# MCUs.net
KiCad netlist of a schematic drawn in Altium Designer
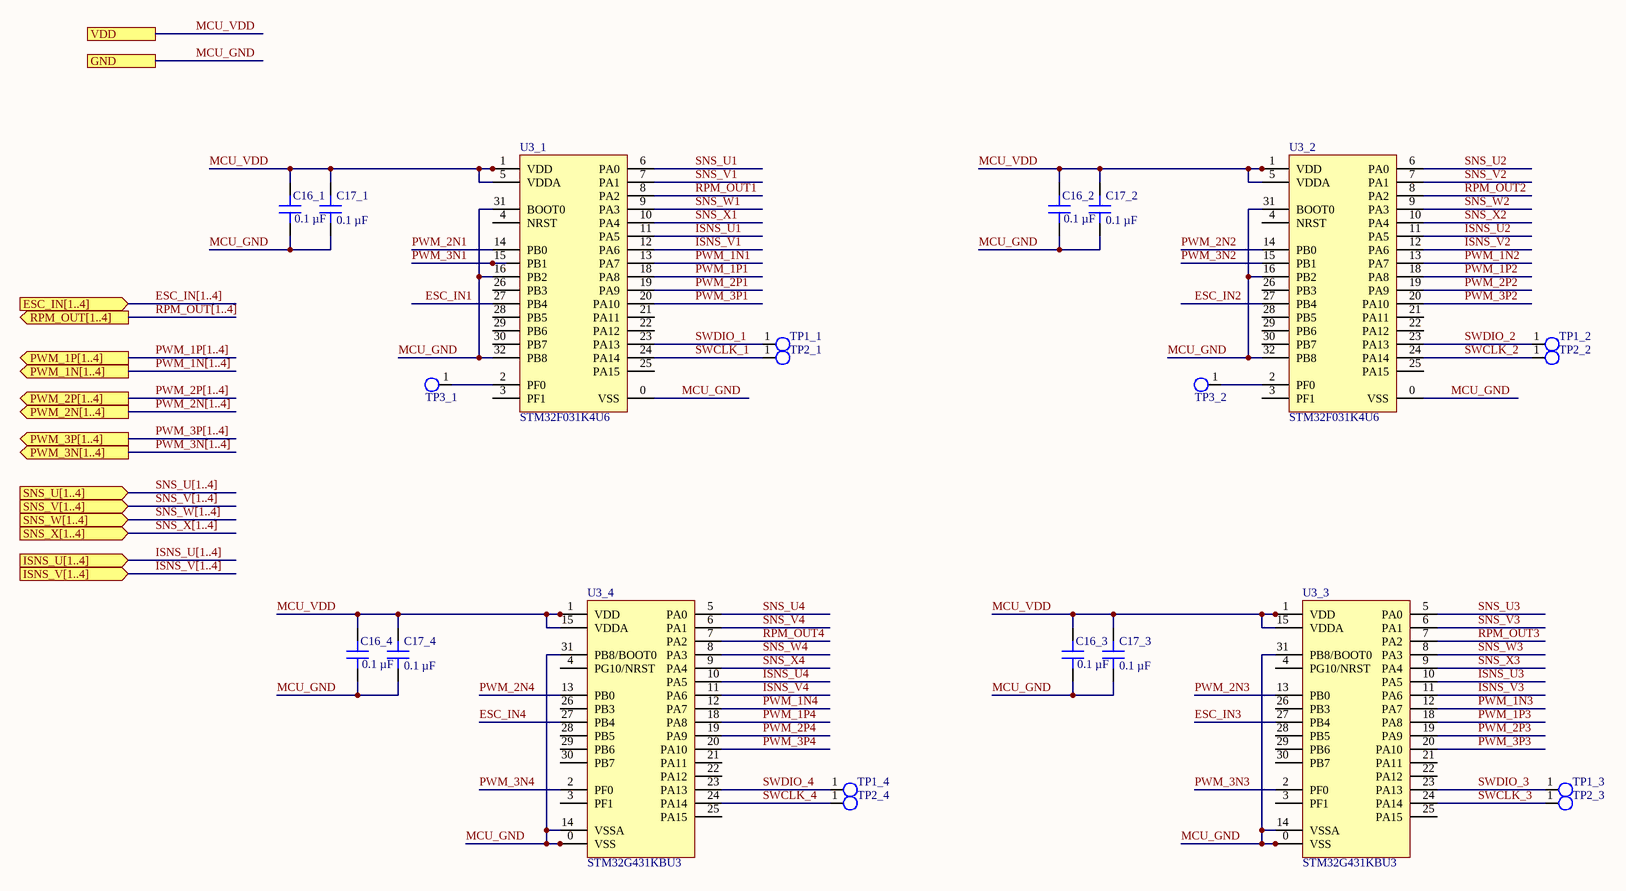
[diagram p0: MCUs.SchDoc]

(export (version "E")
  (design (tool "Eeschema 10.0.6"))
  (components
    (comp (ref "C16_1")
      (value "0.1 µF")
      (footprint "CAP 0402_1005")
      (description "CAP CER 0.1UF 16V X7R 0402")
      (fields (field (name "PART NUMBER") "C0402C104K4RACAUTO") (field (name "MANUFACTURER") "KEMET"))
      (libsource (lib "Celestial Altium Library - altium_library") (part "Capacitor"))
    )
    (comp (ref "C16_2")
      (value "0.1 µF")
      (footprint "CAP 0402_1005")
      (description "CAP CER 0.1UF 16V X7R 0402")
      (fields (field (name "PART NUMBER") "C0402C104K4RACAUTO") (field (name "MANUFACTURER") "KEMET"))
      (libsource (lib "Celestial Altium Library - altium_library") (part "Capacitor"))
    )
    (comp (ref "C16_3")
      (value "0.1 µF")
      (footprint "CAP 0402_1005")
      (description "CAP CER 0.1UF 16V X7R 0402")
      (fields (field (name "PART NUMBER") "C0402C104K4RACAUTO") (field (name "MANUFACTURER") "KEMET"))
      (libsource (lib "Celestial Altium Library - altium_library") (part "Capacitor"))
    )
    (comp (ref "C16_4")
      (value "0.1 µF")
      (footprint "CAP 0402_1005")
      (description "CAP CER 0.1UF 16V X7R 0402")
      (fields (field (name "PART NUMBER") "C0402C104K4RACAUTO") (field (name "MANUFACTURER") "KEMET"))
      (libsource (lib "Celestial Altium Library - altium_library") (part "Capacitor"))
    )
    (comp (ref "C17_1")
      (value "0.1 µF")
      (footprint "CAP 0402_1005")
      (description "CAP CER 0.1UF 16V X7R 0402")
      (fields (field (name "PART NUMBER") "C0402C104K4RACAUTO") (field (name "MANUFACTURER") "KEMET"))
      (libsource (lib "Celestial Altium Library - altium_library") (part "Capacitor"))
    )
    (comp (ref "C17_2")
      (value "0.1 µF")
      (footprint "CAP 0402_1005")
      (description "CAP CER 0.1UF 16V X7R 0402")
      (fields (field (name "PART NUMBER") "C0402C104K4RACAUTO") (field (name "MANUFACTURER") "KEMET"))
      (libsource (lib "Celestial Altium Library - altium_library") (part "Capacitor"))
    )
    (comp (ref "C17_3")
      (value "0.1 µF")
      (footprint "CAP 0402_1005")
      (description "CAP CER 0.1UF 16V X7R 0402")
      (fields (field (name "PART NUMBER") "C0402C104K4RACAUTO") (field (name "MANUFACTURER") "KEMET"))
      (libsource (lib "Celestial Altium Library - altium_library") (part "Capacitor"))
    )
    (comp (ref "C17_4")
      (value "0.1 µF")
      (footprint "CAP 0402_1005")
      (description "CAP CER 0.1UF 16V X7R 0402")
      (fields (field (name "PART NUMBER") "C0402C104K4RACAUTO") (field (name "MANUFACTURER") "KEMET"))
      (libsource (lib "Celestial Altium Library - altium_library") (part "Capacitor"))
    )
    (comp (ref "TP1_1")
      (value "0.635mm")
      (footprint "TP  0.635mm")
      (description "Test point")
      (libsource (lib "IC") (part "TP 0.635mm"))
    )
    (comp (ref "TP1_2")
      (value "0.635mm")
      (footprint "TP  0.635mm")
      (description "Test point")
      (libsource (lib "IC") (part "TP 0.635mm"))
    )
    (comp (ref "TP1_3")
      (value "0.635mm")
      (footprint "TP  0.635mm")
      (description "Test point")
      (libsource (lib "IC") (part "TP 0.635mm"))
    )
    (comp (ref "TP1_4")
      (value "0.635mm")
      (footprint "TP  0.635mm")
      (description "Test point")
      (libsource (lib "IC") (part "TP 0.635mm"))
    )
    (comp (ref "TP2_1")
      (value "0.635mm")
      (footprint "TP  0.635mm")
      (description "Test point")
      (libsource (lib "IC") (part "TP 0.635mm"))
    )
    (comp (ref "TP2_2")
      (value "0.635mm")
      (footprint "TP  0.635mm")
      (description "Test point")
      (libsource (lib "IC") (part "TP 0.635mm"))
    )
    (comp (ref "TP2_3")
      (value "0.635mm")
      (footprint "TP  0.635mm")
      (description "Test point")
      (libsource (lib "IC") (part "TP 0.635mm"))
    )
    (comp (ref "TP2_4")
      (value "0.635mm")
      (footprint "TP  0.635mm")
      (description "Test point")
      (libsource (lib "IC") (part "TP 0.635mm"))
    )
    (comp (ref "TP3_1")
      (value "0.635mm")
      (footprint "TP  0.635mm")
      (description "Test point")
      (libsource (lib "IC") (part "TP 0.635mm"))
    )
    (comp (ref "TP3_2")
      (value "0.635mm")
      (footprint "TP  0.635mm")
      (description "Test point")
      (libsource (lib "IC") (part "TP 0.635mm"))
    )
    (comp (ref "U3_1")
      (value "STM32F031K4U6")
      (footprint "QFN50P400X400X60-32N")
      (description "MCU UFQFPN-32")
      (libsource (lib "IC") (part "STM32F031K4U6"))
    )
    (comp (ref "U3_2")
      (value "STM32F031K4U6")
      (footprint "QFN50P400X400X60-32N")
      (description "MCU UFQFPN-32")
      (libsource (lib "IC") (part "STM32F031K4U6"))
    )
    (comp (ref "U3_3")
      (value "STM32G431KBU3")
      (footprint "QFN50P400X400X60-32N")
      (description "MCU UFQFPN-32")
      (libsource (lib "IC") (part "STM32G431KBU3"))
    )
    (comp (ref "U3_4")
      (value "STM32G431KBU3")
      (footprint "QFN50P400X400X60-32N")
      (description "MCU UFQFPN-32")
      (libsource (lib "IC") (part "STM32G431KBU3"))
    )
  )
  (nets
    (net (code "1") (name "/ESC_IN1") (class "Default")
      (node (ref "U3_1") (pin "27") (pinfunction "PB4_27") (pintype "passive"))
    )
    (net (code "2") (name "/ESC_IN2") (class "Default")
      (node (ref "U3_2") (pin "27") (pinfunction "PB4_27") (pintype "passive"))
    )
    (net (code "3") (name "/ESC_IN3") (class "Default")
      (node (ref "U3_3") (pin "27") (pinfunction "PB4_27") (pintype "passive"))
    )
    (net (code "4") (name "/ESC_IN4") (class "Default")
      (node (ref "U3_4") (pin "27") (pinfunction "PB4_27") (pintype "passive"))
    )
    (net (code "6") (name "/ISNS_U1") (class "Default")
      (node (ref "U3_1") (pin "11") (pinfunction "PA5_11") (pintype "passive"))
    )
    (net (code "7") (name "/ISNS_U2") (class "Default")
      (node (ref "U3_2") (pin "11") (pinfunction "PA5_11") (pintype "passive"))
    )
    (net (code "8") (name "/ISNS_U3") (class "Default")
      (node (ref "U3_3") (pin "10") (pinfunction "PA5_10") (pintype "passive"))
    )
    (net (code "9") (name "/ISNS_U4") (class "Default")
      (node (ref "U3_4") (pin "10") (pinfunction "PA5_10") (pintype "passive"))
    )
    (net (code "11") (name "/ISNS_V1") (class "Default")
      (node (ref "U3_1") (pin "12") (pinfunction "PA6_12") (pintype "passive"))
    )
    (net (code "12") (name "/ISNS_V2") (class "Default")
      (node (ref "U3_2") (pin "12") (pinfunction "PA6_12") (pintype "passive"))
    )
    (net (code "13") (name "/ISNS_V3") (class "Default")
      (node (ref "U3_3") (pin "11") (pinfunction "PA6_11") (pintype "passive"))
    )
    (net (code "14") (name "/ISNS_V4") (class "Default")
      (node (ref "U3_4") (pin "11") (pinfunction "PA6_11") (pintype "passive"))
    )
    (net (code "16") (name "/MCU_GND") (class "Default")
      (node (ref "C16_1") (pin "1") (pinfunction "1_1") (pintype "passive"))
      (node (ref "C16_2") (pin "1") (pinfunction "1_1") (pintype "passive"))
      (node (ref "C16_3") (pin "1") (pinfunction "1_1") (pintype "passive"))
      (node (ref "C16_4") (pin "1") (pinfunction "1_1") (pintype "passive"))
      (node (ref "C17_1") (pin "1") (pinfunction "1_1") (pintype "passive"))
      (node (ref "C17_2") (pin "1") (pinfunction "1_1") (pintype "passive"))
      (node (ref "C17_3") (pin "1") (pinfunction "1_1") (pintype "passive"))
      (node (ref "C17_4") (pin "1") (pinfunction "1_1") (pintype "passive"))
      (node (ref "U3_1") (pin "0") (pinfunction "VSS_0") (pintype "passive"))
      (node (ref "U3_1") (pin "16") (pinfunction "PB2_16") (pintype "passive"))
      (node (ref "U3_1") (pin "31") (pinfunction "BOOT0_31") (pintype "passive"))
      (node (ref "U3_1") (pin "32") (pinfunction "PB8_32") (pintype "passive"))
      (node (ref "U3_2") (pin "0") (pinfunction "VSS_0") (pintype "passive"))
      (node (ref "U3_2") (pin "16") (pinfunction "PB2_16") (pintype "passive"))
      (node (ref "U3_2") (pin "31") (pinfunction "BOOT0_31") (pintype "passive"))
      (node (ref "U3_2") (pin "32") (pinfunction "PB8_32") (pintype "passive"))
      (node (ref "U3_3") (pin "0") (pinfunction "VSS_0") (pintype "passive"))
      (node (ref "U3_3") (pin "14") (pinfunction "VSSA_14") (pintype "passive"))
      (node (ref "U3_3") (pin "16") (pinfunction "VSS_16") (pintype "passive"))
      (node (ref "U3_3") (pin "31") (pinfunction "PB8/BOOT0_31") (pintype "passive"))
      (node (ref "U3_3") (pin "32") (pinfunction "VSS_32") (pintype "passive"))
      (node (ref "U3_4") (pin "0") (pinfunction "VSS_0") (pintype "passive"))
      (node (ref "U3_4") (pin "14") (pinfunction "VSSA_14") (pintype "passive"))
      (node (ref "U3_4") (pin "16") (pinfunction "VSS_16") (pintype "passive"))
      (node (ref "U3_4") (pin "31") (pinfunction "PB8/BOOT0_31") (pintype "passive"))
      (node (ref "U3_4") (pin "32") (pinfunction "VSS_32") (pintype "passive"))
    )
    (net (code "17") (name "/MCU_VDD") (class "Default")
      (node (ref "C16_1") (pin "2") (pinfunction "2_2") (pintype "passive"))
      (node (ref "C16_2") (pin "2") (pinfunction "2_2") (pintype "passive"))
      (node (ref "C16_3") (pin "2") (pinfunction "2_2") (pintype "passive"))
      (node (ref "C16_4") (pin "2") (pinfunction "2_2") (pintype "passive"))
      (node (ref "C17_1") (pin "2") (pinfunction "2_2") (pintype "passive"))
      (node (ref "C17_2") (pin "2") (pinfunction "2_2") (pintype "passive"))
      (node (ref "C17_3") (pin "2") (pinfunction "2_2") (pintype "passive"))
      (node (ref "C17_4") (pin "2") (pinfunction "2_2") (pintype "passive"))
      (node (ref "U3_1") (pin "1") (pinfunction "VDD_1") (pintype "passive"))
      (node (ref "U3_1") (pin "17") (pinfunction "VDD_17") (pintype "passive"))
      (node (ref "U3_1") (pin "5") (pinfunction "VDDA_5") (pintype "passive"))
      (node (ref "U3_2") (pin "1") (pinfunction "VDD_1") (pintype "passive"))
      (node (ref "U3_2") (pin "17") (pinfunction "VDD_17") (pintype "passive"))
      (node (ref "U3_2") (pin "5") (pinfunction "VDDA_5") (pintype "passive"))
      (node (ref "U3_3") (pin "1") (pinfunction "VDD_1") (pintype "passive"))
      (node (ref "U3_3") (pin "15") (pinfunction "VDDA_15") (pintype "passive"))
      (node (ref "U3_3") (pin "17") (pinfunction "VDD_17") (pintype "passive"))
      (node (ref "U3_4") (pin "1") (pinfunction "VDD_1") (pintype "passive"))
      (node (ref "U3_4") (pin "15") (pinfunction "VDDA_15") (pintype "passive"))
      (node (ref "U3_4") (pin "17") (pinfunction "VDD_17") (pintype "passive"))
    )
    (net (code "18") (name "/PWM_1N1") (class "Default")
      (node (ref "U3_1") (pin "13") (pinfunction "PA7_13") (pintype "passive"))
    )
    (net (code "19") (name "/PWM_1N2") (class "Default")
      (node (ref "U3_2") (pin "13") (pinfunction "PA7_13") (pintype "passive"))
    )
    (net (code "20") (name "/PWM_1N3") (class "Default")
      (node (ref "U3_3") (pin "12") (pinfunction "PA7_12") (pintype "passive"))
    )
    (net (code "21") (name "/PWM_1N4") (class "Default")
      (node (ref "U3_4") (pin "12") (pinfunction "PA7_12") (pintype "passive"))
    )
    (net (code "23") (name "/PWM_1P1") (class "Default")
      (node (ref "U3_1") (pin "18") (pinfunction "PA8_18") (pintype "passive"))
    )
    (net (code "24") (name "/PWM_1P2") (class "Default")
      (node (ref "U3_2") (pin "18") (pinfunction "PA8_18") (pintype "passive"))
    )
    (net (code "25") (name "/PWM_1P3") (class "Default")
      (node (ref "U3_3") (pin "18") (pinfunction "PA8_18") (pintype "passive"))
    )
    (net (code "26") (name "/PWM_1P4") (class "Default")
      (node (ref "U3_4") (pin "18") (pinfunction "PA8_18") (pintype "passive"))
    )
    (net (code "28") (name "/PWM_2N1") (class "Default")
      (node (ref "U3_1") (pin "14") (pinfunction "PB0_14") (pintype "passive"))
    )
    (net (code "29") (name "/PWM_2N2") (class "Default")
      (node (ref "U3_2") (pin "14") (pinfunction "PB0_14") (pintype "passive"))
    )
    (net (code "30") (name "/PWM_2N3") (class "Default")
      (node (ref "U3_3") (pin "13") (pinfunction "PB0_13") (pintype "passive"))
    )
    (net (code "31") (name "/PWM_2N4") (class "Default")
      (node (ref "U3_4") (pin "13") (pinfunction "PB0_13") (pintype "passive"))
    )
    (net (code "33") (name "/PWM_2P1") (class "Default")
      (node (ref "U3_1") (pin "19") (pinfunction "PA9_19") (pintype "passive"))
    )
    (net (code "34") (name "/PWM_2P2") (class "Default")
      (node (ref "U3_2") (pin "19") (pinfunction "PA9_19") (pintype "passive"))
    )
    (net (code "35") (name "/PWM_2P3") (class "Default")
      (node (ref "U3_3") (pin "19") (pinfunction "PA9_19") (pintype "passive"))
    )
    (net (code "36") (name "/PWM_2P4") (class "Default")
      (node (ref "U3_4") (pin "19") (pinfunction "PA9_19") (pintype "passive"))
    )
    (net (code "38") (name "/PWM_3N1") (class "Default")
      (node (ref "U3_1") (pin "15") (pinfunction "PB1_15") (pintype "passive"))
    )
    (net (code "39") (name "/PWM_3N2") (class "Default")
      (node (ref "U3_2") (pin "15") (pinfunction "PB1_15") (pintype "passive"))
    )
    (net (code "40") (name "/PWM_3N3") (class "Default")
      (node (ref "U3_3") (pin "2") (pinfunction "PF0_2") (pintype "passive"))
    )
    (net (code "41") (name "/PWM_3N4") (class "Default")
      (node (ref "U3_4") (pin "2") (pinfunction "PF0_2") (pintype "passive"))
    )
    (net (code "43") (name "/PWM_3P1") (class "Default")
      (node (ref "U3_1") (pin "20") (pinfunction "PA10_20") (pintype "passive"))
    )
    (net (code "44") (name "/PWM_3P2") (class "Default")
      (node (ref "U3_2") (pin "20") (pinfunction "PA10_20") (pintype "passive"))
    )
    (net (code "45") (name "/PWM_3P3") (class "Default")
      (node (ref "U3_3") (pin "20") (pinfunction "PA10_20") (pintype "passive"))
    )
    (net (code "46") (name "/PWM_3P4") (class "Default")
      (node (ref "U3_4") (pin "20") (pinfunction "PA10_20") (pintype "passive"))
    )
    (net (code "48") (name "/RPM_OUT1") (class "Default")
      (node (ref "U3_1") (pin "8") (pinfunction "PA2_8") (pintype "passive"))
    )
    (net (code "49") (name "/RPM_OUT2") (class "Default")
      (node (ref "U3_2") (pin "8") (pinfunction "PA2_8") (pintype "passive"))
    )
    (net (code "50") (name "/RPM_OUT3") (class "Default")
      (node (ref "U3_3") (pin "7") (pinfunction "PA2_7") (pintype "passive"))
    )
    (net (code "51") (name "/RPM_OUT4") (class "Default")
      (node (ref "U3_4") (pin "7") (pinfunction "PA2_7") (pintype "passive"))
    )
    (net (code "53") (name "/SNS_U1") (class "Default")
      (node (ref "U3_1") (pin "6") (pinfunction "PA0_6") (pintype "passive"))
    )
    (net (code "54") (name "/SNS_U2") (class "Default")
      (node (ref "U3_2") (pin "6") (pinfunction "PA0_6") (pintype "passive"))
    )
    (net (code "55") (name "/SNS_U3") (class "Default")
      (node (ref "U3_3") (pin "5") (pinfunction "PA0_5") (pintype "passive"))
    )
    (net (code "56") (name "/SNS_U4") (class "Default")
      (node (ref "U3_4") (pin "5") (pinfunction "PA0_5") (pintype "passive"))
    )
    (net (code "58") (name "/SNS_V1") (class "Default")
      (node (ref "U3_1") (pin "7") (pinfunction "PA1_7") (pintype "passive"))
    )
    (net (code "59") (name "/SNS_V2") (class "Default")
      (node (ref "U3_2") (pin "7") (pinfunction "PA1_7") (pintype "passive"))
    )
    (net (code "60") (name "/SNS_V3") (class "Default")
      (node (ref "U3_3") (pin "6") (pinfunction "PA1_6") (pintype "passive"))
    )
    (net (code "61") (name "/SNS_V4") (class "Default")
      (node (ref "U3_4") (pin "6") (pinfunction "PA1_6") (pintype "passive"))
    )
    (net (code "63") (name "/SNS_W1") (class "Default")
      (node (ref "U3_1") (pin "9") (pinfunction "PA3_9") (pintype "passive"))
    )
    (net (code "64") (name "/SNS_W2") (class "Default")
      (node (ref "U3_2") (pin "9") (pinfunction "PA3_9") (pintype "passive"))
    )
    (net (code "65") (name "/SNS_W3") (class "Default")
      (node (ref "U3_3") (pin "8") (pinfunction "PA3_8") (pintype "passive"))
    )
    (net (code "66") (name "/SNS_W4") (class "Default")
      (node (ref "U3_4") (pin "8") (pinfunction "PA3_8") (pintype "passive"))
    )
    (net (code "68") (name "/SNS_X1") (class "Default")
      (node (ref "U3_1") (pin "10") (pinfunction "PA4_10") (pintype "passive"))
    )
    (net (code "69") (name "/SNS_X2") (class "Default")
      (node (ref "U3_2") (pin "10") (pinfunction "PA4_10") (pintype "passive"))
    )
    (net (code "70") (name "/SNS_X3") (class "Default")
      (node (ref "U3_3") (pin "9") (pinfunction "PA4_9") (pintype "passive"))
    )
    (net (code "71") (name "/SNS_X4") (class "Default")
      (node (ref "U3_4") (pin "9") (pinfunction "PA4_9") (pintype "passive"))
    )
    (net (code "73") (name "/SWCLK_1") (class "Default")
      (node (ref "TP2_1") (pin "1") (pinfunction "TP_1") (pintype "passive"))
      (node (ref "U3_1") (pin "24") (pinfunction "PA14_24") (pintype "passive"))
    )
    (net (code "74") (name "/SWCLK_2") (class "Default")
      (node (ref "TP2_2") (pin "1") (pinfunction "TP_1") (pintype "passive"))
      (node (ref "U3_2") (pin "24") (pinfunction "PA14_24") (pintype "passive"))
    )
    (net (code "75") (name "/SWCLK_3") (class "Default")
      (node (ref "TP2_3") (pin "1") (pinfunction "TP_1") (pintype "passive"))
      (node (ref "U3_3") (pin "24") (pinfunction "PA14_24") (pintype "passive"))
    )
    (net (code "76") (name "/SWCLK_4") (class "Default")
      (node (ref "TP2_4") (pin "1") (pinfunction "TP_1") (pintype "passive"))
      (node (ref "U3_4") (pin "24") (pinfunction "PA14_24") (pintype "passive"))
    )
    (net (code "77") (name "/SWDIO_1") (class "Default")
      (node (ref "TP1_1") (pin "1") (pinfunction "TP_1") (pintype "passive"))
      (node (ref "U3_1") (pin "23") (pinfunction "PA13_23") (pintype "passive"))
    )
    (net (code "78") (name "/SWDIO_2") (class "Default")
      (node (ref "TP1_2") (pin "1") (pinfunction "TP_1") (pintype "passive"))
      (node (ref "U3_2") (pin "23") (pinfunction "PA13_23") (pintype "passive"))
    )
    (net (code "79") (name "/SWDIO_3") (class "Default")
      (node (ref "TP1_3") (pin "1") (pinfunction "TP_1") (pintype "passive"))
      (node (ref "U3_3") (pin "23") (pinfunction "PA13_23") (pintype "passive"))
    )
    (net (code "80") (name "/SWDIO_4") (class "Default")
      (node (ref "TP1_4") (pin "1") (pinfunction "TP_1") (pintype "passive"))
      (node (ref "U3_4") (pin "23") (pinfunction "PA13_23") (pintype "passive"))
    )
    (net (code "81") (name "Net-(TP3_1-TP)") (class "Default")
      (node (ref "TP3_1") (pin "1") (pinfunction "TP_1") (pintype "passive"))
      (node (ref "U3_1") (pin "2") (pinfunction "PF0_2") (pintype "passive"))
    )
    (net (code "82") (name "Net-(TP3_2-TP)") (class "Default")
      (node (ref "TP3_2") (pin "1") (pinfunction "TP_1") (pintype "passive"))
      (node (ref "U3_2") (pin "2") (pinfunction "PF0_2") (pintype "passive"))
    )
    (net (code "83") (name "unconnected-(U3_1-NRST-Pad4)") (class "Default")
      (node (ref "U3_1") (pin "4") (pinfunction "NRST_4") (pintype "passive"))
    )
    (net (code "84") (name "unconnected-(U3_1-PA11-Pad21)") (class "Default")
      (node (ref "U3_1") (pin "21") (pinfunction "PA11_21") (pintype "passive"))
    )
    (net (code "85") (name "unconnected-(U3_1-PA12-Pad22)") (class "Default")
      (node (ref "U3_1") (pin "22") (pinfunction "PA12_22") (pintype "passive"))
    )
    (net (code "86") (name "unconnected-(U3_1-PA15-Pad25)") (class "Default")
      (node (ref "U3_1") (pin "25") (pinfunction "PA15_25") (pintype "passive"))
    )
    (net (code "87") (name "unconnected-(U3_1-PB3-Pad26)") (class "Default")
      (node (ref "U3_1") (pin "26") (pinfunction "PB3_26") (pintype "passive"))
    )
    (net (code "88") (name "unconnected-(U3_1-PB5-Pad28)") (class "Default")
      (node (ref "U3_1") (pin "28") (pinfunction "PB5_28") (pintype "passive"))
    )
    (net (code "89") (name "unconnected-(U3_1-PB6-Pad29)") (class "Default")
      (node (ref "U3_1") (pin "29") (pinfunction "PB6_29") (pintype "passive"))
    )
    (net (code "90") (name "unconnected-(U3_1-PB7-Pad30)") (class "Default")
      (node (ref "U3_1") (pin "30") (pinfunction "PB7_30") (pintype "passive"))
    )
    (net (code "91") (name "unconnected-(U3_1-PF1-Pad3)") (class "Default")
      (node (ref "U3_1") (pin "3") (pinfunction "PF1_3") (pintype "passive"))
    )
    (net (code "92") (name "unconnected-(U3_2-NRST-Pad4)") (class "Default")
      (node (ref "U3_2") (pin "4") (pinfunction "NRST_4") (pintype "passive"))
    )
    (net (code "93") (name "unconnected-(U3_2-PA11-Pad21)") (class "Default")
      (node (ref "U3_2") (pin "21") (pinfunction "PA11_21") (pintype "passive"))
    )
    (net (code "94") (name "unconnected-(U3_2-PA12-Pad22)") (class "Default")
      (node (ref "U3_2") (pin "22") (pinfunction "PA12_22") (pintype "passive"))
    )
    (net (code "95") (name "unconnected-(U3_2-PA15-Pad25)") (class "Default")
      (node (ref "U3_2") (pin "25") (pinfunction "PA15_25") (pintype "passive"))
    )
    (net (code "96") (name "unconnected-(U3_2-PB3-Pad26)") (class "Default")
      (node (ref "U3_2") (pin "26") (pinfunction "PB3_26") (pintype "passive"))
    )
    (net (code "97") (name "unconnected-(U3_2-PB5-Pad28)") (class "Default")
      (node (ref "U3_2") (pin "28") (pinfunction "PB5_28") (pintype "passive"))
    )
    (net (code "98") (name "unconnected-(U3_2-PB6-Pad29)") (class "Default")
      (node (ref "U3_2") (pin "29") (pinfunction "PB6_29") (pintype "passive"))
    )
    (net (code "99") (name "unconnected-(U3_2-PB7-Pad30)") (class "Default")
      (node (ref "U3_2") (pin "30") (pinfunction "PB7_30") (pintype "passive"))
    )
    (net (code "100") (name "unconnected-(U3_2-PF1-Pad3)") (class "Default")
      (node (ref "U3_2") (pin "3") (pinfunction "PF1_3") (pintype "passive"))
    )
    (net (code "101") (name "unconnected-(U3_3-PA11-Pad21)") (class "Default")
      (node (ref "U3_3") (pin "21") (pinfunction "PA11_21") (pintype "passive"))
    )
    (net (code "102") (name "unconnected-(U3_3-PA12-Pad22)") (class "Default")
      (node (ref "U3_3") (pin "22") (pinfunction "PA12_22") (pintype "passive"))
    )
    (net (code "103") (name "unconnected-(U3_3-PA15-Pad25)") (class "Default")
      (node (ref "U3_3") (pin "25") (pinfunction "PA15_25") (pintype "passive"))
    )
    (net (code "104") (name "unconnected-(U3_3-PB3-Pad26)") (class "Default")
      (node (ref "U3_3") (pin "26") (pinfunction "PB3_26") (pintype "passive"))
    )
    (net (code "105") (name "unconnected-(U3_3-PB5-Pad28)") (class "Default")
      (node (ref "U3_3") (pin "28") (pinfunction "PB5_28") (pintype "passive"))
    )
    (net (code "106") (name "unconnected-(U3_3-PB6-Pad29)") (class "Default")
      (node (ref "U3_3") (pin "29") (pinfunction "PB6_29") (pintype "passive"))
    )
    (net (code "107") (name "unconnected-(U3_3-PB7-Pad30)") (class "Default")
      (node (ref "U3_3") (pin "30") (pinfunction "PB7_30") (pintype "passive"))
    )
    (net (code "108") (name "unconnected-(U3_3-PF1-Pad3)") (class "Default")
      (node (ref "U3_3") (pin "3") (pinfunction "PF1_3") (pintype "passive"))
    )
    (net (code "109") (name "unconnected-(U3_3-PG10{slash}NRST-Pad4)") (class "Default")
      (node (ref "U3_3") (pin "4") (pinfunction "PG10/NRST_4") (pintype "passive"))
    )
    (net (code "110") (name "unconnected-(U3_4-PA11-Pad21)") (class "Default")
      (node (ref "U3_4") (pin "21") (pinfunction "PA11_21") (pintype "passive"))
    )
    (net (code "111") (name "unconnected-(U3_4-PA12-Pad22)") (class "Default")
      (node (ref "U3_4") (pin "22") (pinfunction "PA12_22") (pintype "passive"))
    )
    (net (code "112") (name "unconnected-(U3_4-PA15-Pad25)") (class "Default")
      (node (ref "U3_4") (pin "25") (pinfunction "PA15_25") (pintype "passive"))
    )
    (net (code "113") (name "unconnected-(U3_4-PB3-Pad26)") (class "Default")
      (node (ref "U3_4") (pin "26") (pinfunction "PB3_26") (pintype "passive"))
    )
    (net (code "114") (name "unconnected-(U3_4-PB5-Pad28)") (class "Default")
      (node (ref "U3_4") (pin "28") (pinfunction "PB5_28") (pintype "passive"))
    )
    (net (code "115") (name "unconnected-(U3_4-PB6-Pad29)") (class "Default")
      (node (ref "U3_4") (pin "29") (pinfunction "PB6_29") (pintype "passive"))
    )
    (net (code "116") (name "unconnected-(U3_4-PB7-Pad30)") (class "Default")
      (node (ref "U3_4") (pin "30") (pinfunction "PB7_30") (pintype "passive"))
    )
    (net (code "117") (name "unconnected-(U3_4-PF1-Pad3)") (class "Default")
      (node (ref "U3_4") (pin "3") (pinfunction "PF1_3") (pintype "passive"))
    )
    (net (code "118") (name "unconnected-(U3_4-PG10{slash}NRST-Pad4)") (class "Default")
      (node (ref "U3_4") (pin "4") (pinfunction "PG10/NRST_4") (pintype "passive"))
    )
  )
)
